# remote.net
KiCad netlist of a schematic drawn in EAGLE
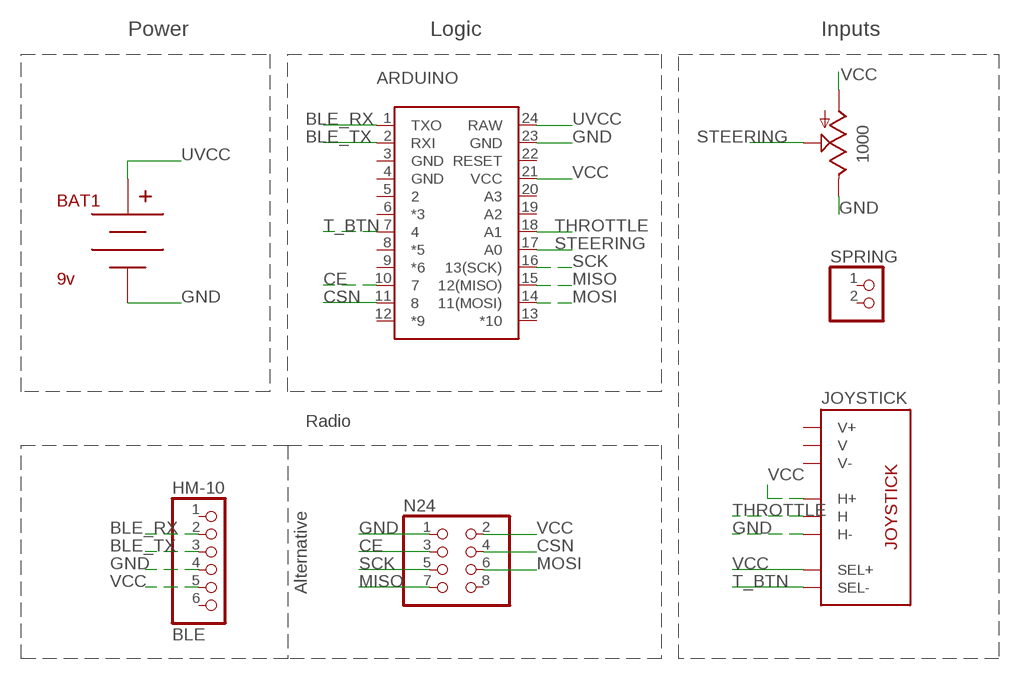
[diagram p0: schematic, sheet 1]

(export (version "E")
  (design (tool "Eeschema 10.0.6"))
  (components
    (comp (ref "ARDUINO")
      (value "ARDUINO_PRO_MICRONORMALNORMAL")
      (footprint "eagle-import:ARDUINO_PRO_MICRO")
      (libsource (lib "eagle-import") (part "ARDUINO_PRO_MICRONORMALNORMAL"))
    )
    (comp (ref "BAT1")
      (value "9v")
      (footprint "eagle-import:BC9VPC")
      (libsource (lib "eagle-import") (part "BC9VPC"))
    )
    (comp (ref "HM-10")
      (value "BLE")
      (footprint "eagle-import:1X06-BIG")
      (libsource (lib "eagle-import") (part "PINHD-1X6B"))
    )
    (comp (ref "JOYSTICK")
      (value "JOYSTICK")
      (footprint "eagle-import:JOYSTICK")
      (libsource (lib "eagle-import") (part "JOYSTICKPTH"))
    )
    (comp (ref "N24")
      (value "NRF24")
      (footprint "eagle-import:2X04")
      (libsource (lib "eagle-import") (part "PINHD-2X4"))
    )
    (comp (ref "RV1")
      (value "1000")
      (footprint "eagle-import:ALPS_POT_2")
      (libsource (lib "eagle-import") (part "POTROBOTITALY"))
    )
    (comp (ref "SPRING")
      (value "PINHD-1X2")
      (footprint "eagle-import:1X02")
      (libsource (lib "eagle-import") (part "PINHD-1X2"))
    )
  )
  (nets
    (net (code "1") (name "/BLE_RX") (class "Default")
      (node (ref "ARDUINO") (pin "1") (pinfunction "TXO_1") (pintype "bidirectional"))
      (node (ref "HM-10") (pin "2") (pinfunction "2_2") (pintype "passive"))
    )
    (net (code "2") (name "/BLE_TX") (class "Default")
      (node (ref "ARDUINO") (pin "2") (pinfunction "RXI_2") (pintype "bidirectional"))
      (node (ref "HM-10") (pin "3") (pinfunction "3_3") (pintype "passive"))
    )
    (net (code "3") (name "/CE") (class "Default")
      (node (ref "ARDUINO") (pin "10") (pinfunction "7_10") (pintype "bidirectional"))
      (node (ref "N24") (pin "3") (pinfunction "3_3") (pintype "passive"))
    )
    (net (code "4") (name "/CSN") (class "Default")
      (node (ref "ARDUINO") (pin "11") (pinfunction "8_11") (pintype "bidirectional"))
      (node (ref "N24") (pin "4") (pinfunction "4_4") (pintype "passive"))
    )
    (net (code "5") (name "/GND") (class "Default")
      (node (ref "ARDUINO") (pin "23") (pinfunction "GND_23") (pintype "bidirectional"))
      (node (ref "BAT1") (pin "V-") (pinfunction "V-_V-") (pintype "bidirectional"))
      (node (ref "HM-10") (pin "4") (pinfunction "4_4") (pintype "passive"))
      (node (ref "JOYSTICK") (pin "H3") (pinfunction "H-_H3") (pintype "bidirectional"))
      (node (ref "N24") (pin "1") (pinfunction "1_1") (pintype "passive"))
      (node (ref "RV1") (pin "P$1") (pinfunction "E_P$1") (pintype "passive"))
    )
    (net (code "6") (name "/MISO") (class "Default")
      (node (ref "ARDUINO") (pin "15") (pinfunction "12(MISO)_15") (pintype "bidirectional"))
      (node (ref "N24") (pin "7") (pinfunction "7_7") (pintype "passive"))
    )
    (net (code "7") (name "/MOSI") (class "Default")
      (node (ref "ARDUINO") (pin "14") (pinfunction "11(MOSI)_14") (pintype "bidirectional"))
      (node (ref "N24") (pin "6") (pinfunction "6_6") (pintype "passive"))
    )
    (net (code "8") (name "/SCK") (class "Default")
      (node (ref "ARDUINO") (pin "16") (pinfunction "13(SCK)_16") (pintype "bidirectional"))
      (node (ref "N24") (pin "5") (pinfunction "5_5") (pintype "passive"))
    )
    (net (code "9") (name "/STEERING") (class "Default")
      (node (ref "ARDUINO") (pin "17") (pinfunction "A0_17") (pintype "bidirectional"))
      (node (ref "RV1") (pin "P$2") (pinfunction "S_P$2") (pintype "passive"))
    )
    (net (code "10") (name "/THROTTLE") (class "Default")
      (node (ref "ARDUINO") (pin "18") (pinfunction "A1_18") (pintype "bidirectional"))
      (node (ref "JOYSTICK") (pin "H2") (pinfunction "H_H2") (pintype "bidirectional"))
    )
    (net (code "11") (name "/T_BTN") (class "Default")
      (node (ref "ARDUINO") (pin "7") (pinfunction "4_7") (pintype "bidirectional"))
      (node (ref "JOYSTICK") (pin "B2A") (pinfunction "SEL-_B2A") (pintype "bidirectional"))
    )
    (net (code "12") (name "/UVCC") (class "Default")
      (node (ref "ARDUINO") (pin "24") (pinfunction "RAW_24") (pintype "bidirectional"))
      (node (ref "BAT1") (pin "V+") (pinfunction "V+_V+") (pintype "bidirectional"))
    )
    (net (code "13") (name "/VCC") (class "Default")
      (node (ref "ARDUINO") (pin "21") (pinfunction "VCC_21") (pintype "bidirectional"))
      (node (ref "HM-10") (pin "5") (pinfunction "5_5") (pintype "passive"))
      (node (ref "JOYSTICK") (pin "B1A") (pinfunction "SEL+_B1A") (pintype "bidirectional"))
      (node (ref "JOYSTICK") (pin "H1") (pinfunction "H+_H1") (pintype "bidirectional"))
      (node (ref "N24") (pin "2") (pinfunction "2_2") (pintype "passive"))
      (node (ref "RV1") (pin "P$3") (pinfunction "A_P$3") (pintype "passive"))
    )
    (net (code "14") (name "unconnected-(ARDUINO-*3-Pad6)") (class "Default")
      (node (ref "ARDUINO") (pin "6") (pinfunction "*3_6") (pintype "bidirectional"))
    )
    (net (code "15") (name "unconnected-(ARDUINO-*5-Pad8)") (class "Default")
      (node (ref "ARDUINO") (pin "8") (pinfunction "*5_8") (pintype "bidirectional"))
    )
    (net (code "16") (name "unconnected-(ARDUINO-*6-Pad9)") (class "Default")
      (node (ref "ARDUINO") (pin "9") (pinfunction "*6_9") (pintype "bidirectional"))
    )
    (net (code "17") (name "unconnected-(ARDUINO-*9-Pad12)") (class "Default")
      (node (ref "ARDUINO") (pin "12") (pinfunction "*9_12") (pintype "bidirectional"))
    )
    (net (code "18") (name "unconnected-(ARDUINO-*10-Pad13)") (class "Default")
      (node (ref "ARDUINO") (pin "13") (pinfunction "*10_13") (pintype "bidirectional"))
    )
    (net (code "19") (name "unconnected-(ARDUINO-2-Pad5)") (class "Default")
      (node (ref "ARDUINO") (pin "5") (pinfunction "2_5") (pintype "bidirectional"))
    )
    (net (code "20") (name "unconnected-(ARDUINO-A2-Pad19)") (class "Default")
      (node (ref "ARDUINO") (pin "19") (pinfunction "A2_19") (pintype "bidirectional"))
    )
    (net (code "21") (name "unconnected-(ARDUINO-A3-Pad20)") (class "Default")
      (node (ref "ARDUINO") (pin "20") (pinfunction "A3_20") (pintype "bidirectional"))
    )
    (net (code "22") (name "unconnected-(ARDUINO-GND-Pad3)") (class "Default")
      (node (ref "ARDUINO") (pin "3") (pinfunction "GND_3") (pintype "bidirectional"))
    )
    (net (code "23") (name "unconnected-(ARDUINO-GND-Pad4)") (class "Default")
      (node (ref "ARDUINO") (pin "4") (pinfunction "GND_4") (pintype "bidirectional"))
    )
    (net (code "24") (name "unconnected-(ARDUINO-RESET-Pad22)") (class "Default")
      (node (ref "ARDUINO") (pin "22") (pinfunction "RESET_22") (pintype "bidirectional"))
    )
    (net (code "25") (name "unconnected-(HM-10-Pad1)") (class "Default")
      (node (ref "HM-10") (pin "1") (pinfunction "1_1") (pintype "passive"))
    )
    (net (code "26") (name "unconnected-(HM-10-Pad6)") (class "Default")
      (node (ref "HM-10") (pin "6") (pinfunction "6_6") (pintype "passive"))
    )
    (net (code "27") (name "unconnected-(JOYSTICK-V+-PadV1)") (class "Default")
      (node (ref "JOYSTICK") (pin "V1") (pinfunction "V+_V1") (pintype "bidirectional"))
    )
    (net (code "28") (name "unconnected-(JOYSTICK-V--PadV3)") (class "Default")
      (node (ref "JOYSTICK") (pin "V3") (pinfunction "V-_V3") (pintype "bidirectional"))
    )
    (net (code "29") (name "unconnected-(JOYSTICK-V-PadV2)") (class "Default")
      (node (ref "JOYSTICK") (pin "V2") (pinfunction "V_V2") (pintype "bidirectional"))
    )
    (net (code "30") (name "unconnected-(N24-Pad8)") (class "Default")
      (node (ref "N24") (pin "8") (pinfunction "8_8") (pintype "passive"))
    )
    (net (code "31") (name "unconnected-(SPRING-Pad1)") (class "Default")
      (node (ref "SPRING") (pin "1") (pinfunction "1_1") (pintype "passive"))
    )
    (net (code "32") (name "unconnected-(SPRING-Pad2)") (class "Default")
      (node (ref "SPRING") (pin "2") (pinfunction "2_2") (pintype "passive"))
    )
  )
)
